# Satshakit_Crab.net
KiCad netlist of a schematic drawn in EAGLE
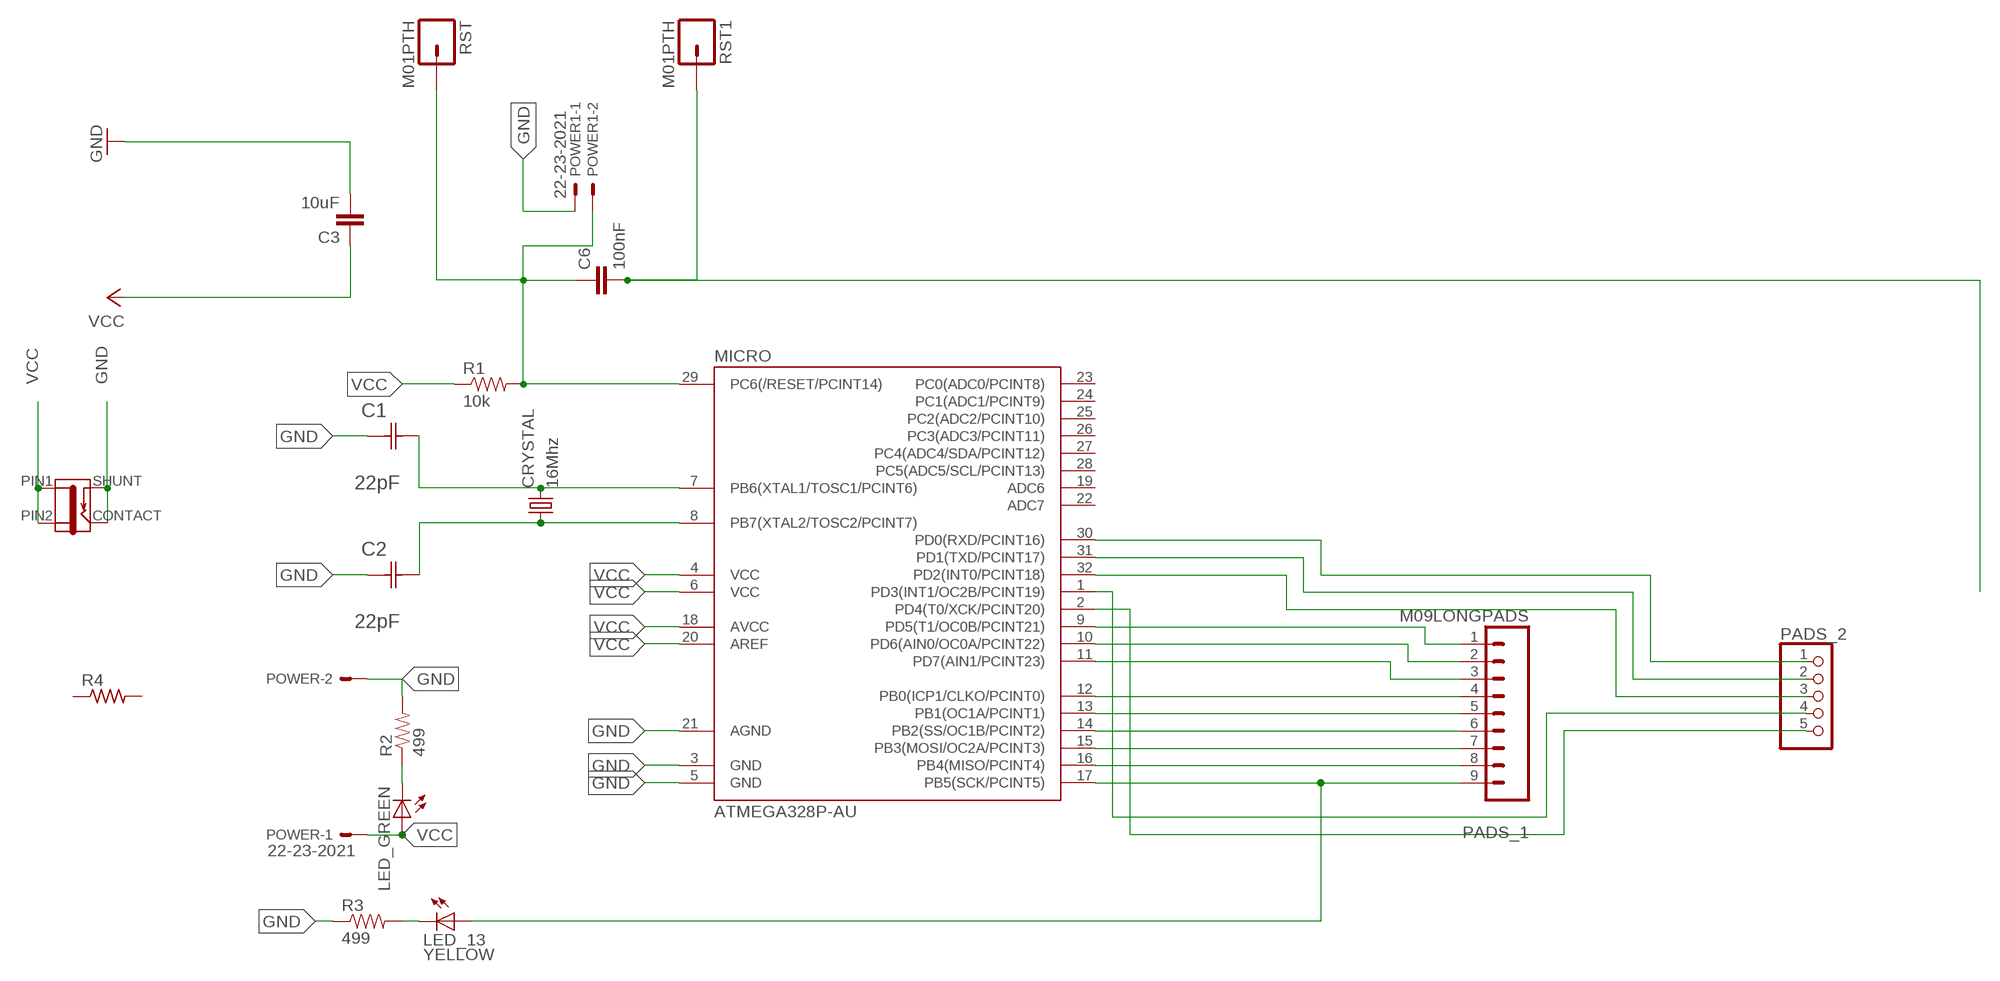
[diagram p0: schematic, sheet 1]

(export (version "E")
  (design (tool "Eeschema 10.0.6"))
  (components
    (comp (ref "C1")
      (value "22pF")
      (footprint "eagle-import:CAPC3216X178N")
      (fields (field (name "MPN") "0612ZC225MAT2A") (field (name "TOLERANCE") "±20%"))
      (libsource (lib "eagle-import") (part "0612ZC225MAT2A"))
    )
    (comp (ref "C2")
      (value "22pF")
      (footprint "eagle-import:CAPC3216X178N")
      (fields (field (name "MPN") "0612ZC225MAT2A") (field (name "TOLERANCE") "±20%"))
      (libsource (lib "eagle-import") (part "0612ZC225MAT2A"))
    )
    (comp (ref "C3")
      (value "10uF")
      (footprint "eagle-import:1206")
      (libsource (lib "eagle-import") (part "CAP1206"))
    )
    (comp (ref "C6")
      (value "100nF")
      (footprint "eagle-import:1206")
      (libsource (lib "eagle-import") (part "CAP1206"))
    )
    (comp (ref "CRYSTAL")
      (value "16Mhz")
      (footprint "eagle-import:CSM-7X-DU")
      (libsource (lib "eagle-import") (part "CSM-7X-DU"))
    )
    (comp (ref "J1")
      (value "JACK-2.1MM")
      (footprint "eagle-import:PJ-002AH-SMT")
      (libsource (lib "eagle-import") (part "JACK-2.1MM"))
    )
    (comp (ref "LED_13")
      (value "YELLOW")
      (footprint "eagle-import:1206")
      (libsource (lib "eagle-import") (part "LED1206"))
    )
    (comp (ref "LED_GREEN")
      (value "LED1206")
      (footprint "eagle-import:1206")
      (libsource (lib "eagle-import") (part "LED1206"))
    )
    (comp (ref "MICRO")
      (value "ATMEGA328P-AU")
      (footprint "eagle-import:TQFP32-08")
      (libsource (lib "eagle-import") (part "ATMEGA48/88/168-AU"))
    )
    (comp (ref "PADS_1")
      (value "M09LONGPADS")
      (footprint "eagle-import:1X09_LONGPADS")
      (libsource (lib "eagle-import") (part "M09LONGPADS"))
    )
    (comp (ref "PADS_2")
      (value "PINHD-1X5")
      (footprint "eagle-import:1X05")
      (libsource (lib "eagle-import") (part "PINHD-1X5"))
    )
    (comp (ref "POWER")
      (value "22-23-2021")
      (footprint "eagle-import:22-23-2021")
      (fields (field (name "MF") "MOLEX"))
      (libsource (lib "eagle-import") (part "22-23-2021"))
    )
    (comp (ref "POWER1")
      (value "22-23-2021")
      (footprint "eagle-import:22-23-2021")
      (fields (field (name "MF") "MOLEX"))
      (libsource (lib "eagle-import") (part "22-23-2021"))
    )
    (comp (ref "R1")
      (value "10k")
      (footprint "eagle-import:1206")
      (libsource (lib "eagle-import") (part "RESISTOR1206"))
    )
    (comp (ref "R2")
      (value "499")
      (footprint "eagle-import:1206")
      (libsource (lib "eagle-import") (part "RESISTOR1206"))
    )
    (comp (ref "R3")
      (value "499")
      (footprint "eagle-import:1206")
      (libsource (lib "eagle-import") (part "RESISTOR1206"))
    )
    (comp (ref "R4")
      (value "RES-US1206FAB")
      (footprint "eagle-import:R1206FAB")
      (libsource (lib "eagle-import") (part "RES-US1206FAB"))
    )
    (comp (ref "RST")
      (value "M01PTH")
      (footprint "eagle-import:1X01")
      (libsource (lib "eagle-import") (part "M01PTH"))
    )
    (comp (ref "RST1")
      (value "M01PTH")
      (footprint "eagle-import:1X01")
      (libsource (lib "eagle-import") (part "M01PTH"))
    )
  )
  (nets
    (net (code "1") (name "GND") (class "Default")
      (node (ref "C1") (pin "1") (pinfunction "C1_1") (pintype "passive"))
      (node (ref "C2") (pin "1") (pinfunction "C1_1") (pintype "passive"))
      (node (ref "C3") (pin "2") (pinfunction "2_2") (pintype "passive"))
      (node (ref "J1") (pin "CONTACT") (pinfunction "CONTACT_CONTACT") (pintype "power_in"))
      (node (ref "J1") (pin "SHUNT") (pinfunction "SHUNT_SHUNT") (pintype "power_in"))
      (node (ref "MICRO") (pin "21") (pinfunction "AGND_21") (pintype "power_in"))
      (node (ref "MICRO") (pin "3") (pinfunction "GND_3") (pintype "power_in"))
      (node (ref "MICRO") (pin "5") (pinfunction "GND_5") (pintype "power_in"))
      (node (ref "POWER") (pin "2") (pinfunction "S_2") (pintype "passive"))
      (node (ref "POWER1") (pin "1") (pinfunction "S_1") (pintype "passive"))
      (node (ref "R2") (pin "2") (pinfunction "2_2") (pintype "passive"))
      (node (ref "R3") (pin "1") (pinfunction "1_1") (pintype "passive"))
    )
    (net (code "2") (name "Net-(C1-C2)") (class "Default")
      (node (ref "C1") (pin "2") (pinfunction "C2_2") (pintype "passive"))
      (node (ref "CRYSTAL") (pin "2") (pinfunction "2_2") (pintype "passive"))
      (node (ref "MICRO") (pin "7") (pinfunction "PB6(XTAL1/TOSC1/PCINT6)_7") (pintype "bidirectional"))
    )
    (net (code "3") (name "Net-(C2-C2)") (class "Default")
      (node (ref "C2") (pin "2") (pinfunction "C2_2") (pintype "passive"))
      (node (ref "CRYSTAL") (pin "1") (pinfunction "1_1") (pintype "passive"))
      (node (ref "MICRO") (pin "8") (pinfunction "PB7(XTAL2/TOSC2/PCINT7)_8") (pintype "bidirectional"))
    )
    (net (code "4") (name "Net-(C6-Pad2)") (class "Default")
      (node (ref "C6") (pin "2") (pinfunction "2_2") (pintype "passive"))
      (node (ref "RST1") (pin "1") (pinfunction "1_1") (pintype "passive"))
    )
    (net (code "5") (name "Net-(LED_13-A)") (class "Default")
      (node (ref "LED_13") (pin "1") (pinfunction "A_1") (pintype "passive"))
      (node (ref "MICRO") (pin "17") (pinfunction "PB5(SCK/PCINT5)_17") (pintype "bidirectional"))
      (node (ref "PADS_1") (pin "9") (pinfunction "9_9") (pintype "passive"))
    )
    (net (code "6") (name "Net-(LED_13-C)") (class "Default")
      (node (ref "LED_13") (pin "2") (pinfunction "C_2") (pintype "passive"))
      (node (ref "R3") (pin "2") (pinfunction "2_2") (pintype "passive"))
    )
    (net (code "7") (name "Net-(LED_GREEN-C)") (class "Default")
      (node (ref "LED_GREEN") (pin "2") (pinfunction "C_2") (pintype "passive"))
      (node (ref "R2") (pin "1") (pinfunction "1_1") (pintype "passive"))
    )
    (net (code "8") (name "Net-(MICRO-PB0(ICP1{slash}CLKO{slash}PCINT0))") (class "Default")
      (node (ref "MICRO") (pin "12") (pinfunction "PB0(ICP1/CLKO/PCINT0)_12") (pintype "bidirectional"))
      (node (ref "PADS_1") (pin "4") (pinfunction "4_4") (pintype "passive"))
    )
    (net (code "9") (name "Net-(MICRO-PB1(OC1A{slash}PCINT1))") (class "Default")
      (node (ref "MICRO") (pin "13") (pinfunction "PB1(OC1A/PCINT1)_13") (pintype "bidirectional"))
      (node (ref "PADS_1") (pin "5") (pinfunction "5_5") (pintype "passive"))
    )
    (net (code "10") (name "Net-(MICRO-PB2(SS{slash}OC1B{slash}PCINT2))") (class "Default")
      (node (ref "MICRO") (pin "14") (pinfunction "PB2(SS/OC1B/PCINT2)_14") (pintype "bidirectional"))
      (node (ref "PADS_1") (pin "6") (pinfunction "6_6") (pintype "passive"))
    )
    (net (code "11") (name "Net-(MICRO-PB3(MOSI{slash}OC2A{slash}PCINT3))") (class "Default")
      (node (ref "MICRO") (pin "15") (pinfunction "PB3(MOSI/OC2A/PCINT3)_15") (pintype "bidirectional"))
      (node (ref "PADS_1") (pin "7") (pinfunction "7_7") (pintype "passive"))
    )
    (net (code "12") (name "Net-(MICRO-PB4(MISO{slash}PCINT4))") (class "Default")
      (node (ref "MICRO") (pin "16") (pinfunction "PB4(MISO/PCINT4)_16") (pintype "bidirectional"))
      (node (ref "PADS_1") (pin "8") (pinfunction "8_8") (pintype "passive"))
    )
    (net (code "13") (name "Net-(MICRO-PC6({slash}RESET{slash}PCINT14))") (class "Default")
      (node (ref "C6") (pin "1") (pinfunction "1_1") (pintype "passive"))
      (node (ref "MICRO") (pin "29") (pinfunction "PC6(/RESET/PCINT14)_29") (pintype "bidirectional"))
      (node (ref "POWER1") (pin "2") (pinfunction "S_2") (pintype "passive"))
      (node (ref "R1") (pin "2") (pinfunction "2_2") (pintype "passive"))
      (node (ref "RST") (pin "1") (pinfunction "1_1") (pintype "passive"))
    )
    (net (code "14") (name "Net-(MICRO-PD0(RXD{slash}PCINT16))") (class "Default")
      (node (ref "MICRO") (pin "30") (pinfunction "PD0(RXD/PCINT16)_30") (pintype "bidirectional"))
      (node (ref "PADS_2") (pin "1") (pinfunction "1_1") (pintype "passive"))
    )
    (net (code "15") (name "Net-(MICRO-PD1(TXD{slash}PCINT17))") (class "Default")
      (node (ref "MICRO") (pin "31") (pinfunction "PD1(TXD/PCINT17)_31") (pintype "bidirectional"))
      (node (ref "PADS_2") (pin "2") (pinfunction "2_2") (pintype "passive"))
    )
    (net (code "16") (name "Net-(MICRO-PD2(INT0{slash}PCINT18))") (class "Default")
      (node (ref "MICRO") (pin "32") (pinfunction "PD2(INT0/PCINT18)_32") (pintype "bidirectional"))
      (node (ref "PADS_2") (pin "3") (pinfunction "3_3") (pintype "passive"))
    )
    (net (code "17") (name "Net-(MICRO-PD3(INT1{slash}OC2B{slash}PCINT19))") (class "Default")
      (node (ref "MICRO") (pin "1") (pinfunction "PD3(INT1/OC2B/PCINT19)_1") (pintype "bidirectional"))
      (node (ref "PADS_2") (pin "4") (pinfunction "4_4") (pintype "passive"))
    )
    (net (code "18") (name "Net-(MICRO-PD4(T0{slash}XCK{slash}PCINT20))") (class "Default")
      (node (ref "MICRO") (pin "2") (pinfunction "PD4(T0/XCK/PCINT20)_2") (pintype "bidirectional"))
      (node (ref "PADS_2") (pin "5") (pinfunction "5_5") (pintype "passive"))
    )
    (net (code "19") (name "Net-(MICRO-PD5(T1{slash}OC0B{slash}PCINT21))") (class "Default")
      (node (ref "MICRO") (pin "9") (pinfunction "PD5(T1/OC0B/PCINT21)_9") (pintype "bidirectional"))
      (node (ref "PADS_1") (pin "1") (pinfunction "1_1") (pintype "passive"))
    )
    (net (code "20") (name "Net-(MICRO-PD6(AIN0{slash}OC0A{slash}PCINT22))") (class "Default")
      (node (ref "MICRO") (pin "10") (pinfunction "PD6(AIN0/OC0A/PCINT22)_10") (pintype "bidirectional"))
      (node (ref "PADS_1") (pin "2") (pinfunction "2_2") (pintype "passive"))
    )
    (net (code "21") (name "Net-(MICRO-PD7(AIN1{slash}PCINT23))") (class "Default")
      (node (ref "MICRO") (pin "11") (pinfunction "PD7(AIN1/PCINT23)_11") (pintype "bidirectional"))
      (node (ref "PADS_1") (pin "3") (pinfunction "3_3") (pintype "passive"))
    )
    (net (code "22") (name "VCC") (class "Default")
      (node (ref "C3") (pin "1") (pinfunction "1_1") (pintype "passive"))
      (node (ref "J1") (pin "PIN1") (pinfunction "PIN1_PIN1") (pintype "power_in"))
      (node (ref "J1") (pin "PIN2") (pinfunction "PIN2_PIN2") (pintype "power_in"))
      (node (ref "LED_GREEN") (pin "1") (pinfunction "A_1") (pintype "passive"))
      (node (ref "MICRO") (pin "18") (pinfunction "AVCC_18") (pintype "passive"))
      (node (ref "MICRO") (pin "20") (pinfunction "AREF_20") (pintype "passive"))
      (node (ref "MICRO") (pin "4") (pinfunction "VCC_4") (pintype "power_in"))
      (node (ref "MICRO") (pin "6") (pinfunction "VCC_6") (pintype "power_in"))
      (node (ref "POWER") (pin "1") (pinfunction "S_1") (pintype "passive"))
      (node (ref "R1") (pin "1") (pinfunction "1_1") (pintype "passive"))
    )
    (net (code "23") (name "unconnected-(MICRO-ADC6-Pad19)") (class "Default")
      (node (ref "MICRO") (pin "19") (pinfunction "ADC6_19") (pintype "passive"))
    )
    (net (code "24") (name "unconnected-(MICRO-ADC7-Pad22)") (class "Default")
      (node (ref "MICRO") (pin "22") (pinfunction "ADC7_22") (pintype "passive"))
    )
    (net (code "25") (name "unconnected-(MICRO-PC0(ADC0{slash}PCINT8)-Pad23)") (class "Default")
      (node (ref "MICRO") (pin "23") (pinfunction "PC0(ADC0/PCINT8)_23") (pintype "bidirectional"))
    )
    (net (code "26") (name "unconnected-(MICRO-PC1(ADC1{slash}PCINT9)-Pad24)") (class "Default")
      (node (ref "MICRO") (pin "24") (pinfunction "PC1(ADC1/PCINT9)_24") (pintype "bidirectional"))
    )
    (net (code "27") (name "unconnected-(MICRO-PC2(ADC2{slash}PCINT10)-Pad25)") (class "Default")
      (node (ref "MICRO") (pin "25") (pinfunction "PC2(ADC2/PCINT10)_25") (pintype "bidirectional"))
    )
    (net (code "28") (name "unconnected-(MICRO-PC3(ADC3{slash}PCINT11)-Pad26)") (class "Default")
      (node (ref "MICRO") (pin "26") (pinfunction "PC3(ADC3/PCINT11)_26") (pintype "bidirectional"))
    )
    (net (code "29") (name "unconnected-(MICRO-PC4(ADC4{slash}SDA{slash}PCINT12)-Pad27)") (class "Default")
      (node (ref "MICRO") (pin "27") (pinfunction "PC4(ADC4/SDA/PCINT12)_27") (pintype "bidirectional"))
    )
    (net (code "30") (name "unconnected-(MICRO-PC5(ADC5{slash}SCL{slash}PCINT13)-Pad28)") (class "Default")
      (node (ref "MICRO") (pin "28") (pinfunction "PC5(ADC5/SCL/PCINT13)_28") (pintype "bidirectional"))
    )
    (net (code "31") (name "unconnected-(R4-Pad1)") (class "Default")
      (node (ref "R4") (pin "1") (pinfunction "1_1") (pintype "passive"))
    )
    (net (code "32") (name "unconnected-(R4-Pad2)") (class "Default")
      (node (ref "R4") (pin "2") (pinfunction "2_2") (pintype "passive"))
    )
  )
)
